# mippe_base.net
KiCad netlist of a schematic drawn in EAGLE
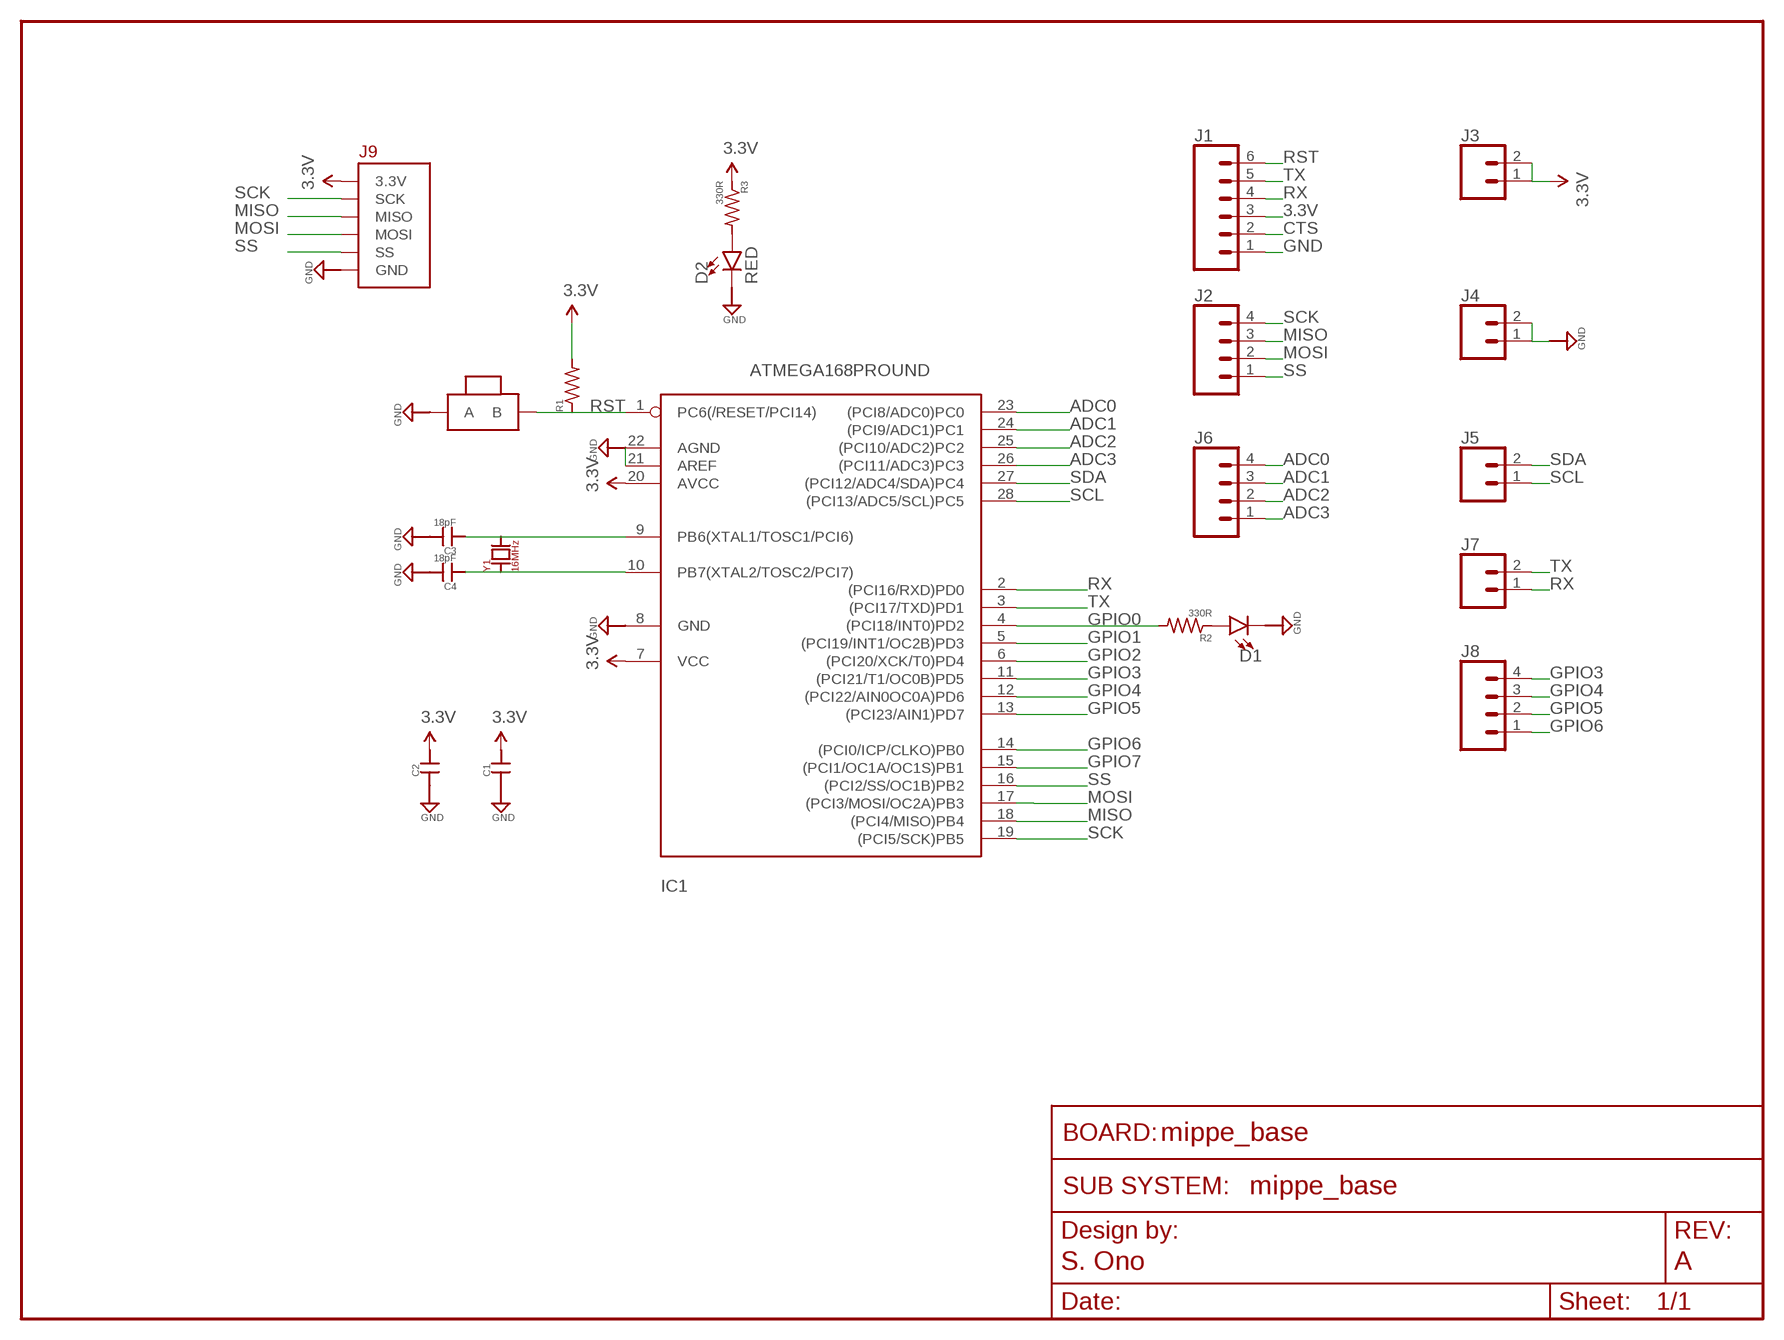
[diagram p0: schematic, sheet 1]

(export (version "E")
  (design (tool "Eeschema 10.0.6"))
  (components
    (comp (ref "C1")
      (value "CAP0603-CAP")
      (footprint "eagle-import:0603-CAP")
      (libsource (lib "eagle-import") (part "CAP0603-CAP"))
    )
    (comp (ref "C2")
      (value "CAP0603-CAP")
      (footprint "eagle-import:0603-CAP")
      (libsource (lib "eagle-import") (part "CAP0603-CAP"))
    )
    (comp (ref "C3")
      (value "18pF")
      (footprint "eagle-import:0603-CAP")
      (libsource (lib "eagle-import") (part "CAP0603-CAP"))
    )
    (comp (ref "C4")
      (value "18pF")
      (footprint "eagle-import:0603-CAP")
      (libsource (lib "eagle-import") (part "CAP0603-CAP"))
    )
    (comp (ref "D1")
      (value "LED0603")
      (footprint "eagle-import:LED-0603")
      (libsource (lib "eagle-import") (part "LED0603"))
    )
    (comp (ref "D2")
      (value "RED")
      (footprint "eagle-import:LED-0603")
      (libsource (lib "eagle-import") (part "LED0603"))
    )
    (comp (ref "IC1")
      (value "ATMEGA168PROUND")
      (footprint "eagle-import:DIL28-3-ROUND")
      (libsource (lib "eagle-import") (part "ATMEGA168PROUND"))
    )
    (comp (ref "J1")
      (value "CONN_06NO_SILK_FEMALE_PTH")
      (footprint "eagle-import:1X06_NO_SILK")
      (libsource (lib "eagle-import") (part "CONN_06NO_SILK_FEMALE_PTH"))
    )
    (comp (ref "J2")
      (value "CONN_041X04_NO_SILK")
      (footprint "eagle-import:1X04_NO_SILK")
      (libsource (lib "eagle-import") (part "CONN_041X04_NO_SILK"))
    )
    (comp (ref "J3")
      (value "CONN_021X02_NO_SILK")
      (footprint "eagle-import:1X02_NO_SILK")
      (libsource (lib "eagle-import") (part "CONN_021X02_NO_SILK"))
    )
    (comp (ref "J4")
      (value "CONN_021X02_NO_SILK")
      (footprint "eagle-import:1X02_NO_SILK")
      (libsource (lib "eagle-import") (part "CONN_021X02_NO_SILK"))
    )
    (comp (ref "J5")
      (value "CONN_021X02_NO_SILK")
      (footprint "eagle-import:1X02_NO_SILK")
      (libsource (lib "eagle-import") (part "CONN_021X02_NO_SILK"))
    )
    (comp (ref "J6")
      (value "CONN_041X04_NO_SILK")
      (footprint "eagle-import:1X04_NO_SILK")
      (libsource (lib "eagle-import") (part "CONN_041X04_NO_SILK"))
    )
    (comp (ref "J7")
      (value "CONN_021X02_NO_SILK")
      (footprint "eagle-import:1X02_NO_SILK")
      (libsource (lib "eagle-import") (part "CONN_021X02_NO_SILK"))
    )
    (comp (ref "J8")
      (value "CONN_041X04_NO_SILK")
      (footprint "eagle-import:1X04_NO_SILK")
      (libsource (lib "eagle-import") (part "CONN_041X04_NO_SILK"))
    )
    (comp (ref "J9")
      (value "BURNIN")
      (footprint "eagle-import:BURNIN")
      (libsource (lib "eagle-import") (part "BURNIN"))
    )
    (comp (ref "R1")
      (value "R-US_R0603")
      (footprint "eagle-import:R0603")
      (fields (field (name "MANUFACTURER") "Rohm Semiconductor"))
      (libsource (lib "eagle-import") (part "R-US_R0603"))
    )
    (comp (ref "R2")
      (value "330R")
      (footprint "eagle-import:R0603")
      (fields (field (name "MANUFACTURER") "Rohm Semiconductor"))
      (libsource (lib "eagle-import") (part "R-US_R0603"))
    )
    (comp (ref "R3")
      (value "330R")
      (footprint "eagle-import:R0603")
      (fields (field (name "MANUFACTURER") "Rohm Semiconductor"))
      (libsource (lib "eagle-import") (part "R-US_R0603"))
    )
    (comp (ref "SW1")
      (value "BTN-PTS810")
      (footprint "eagle-import:BTN_PTS810")
      (libsource (lib "eagle-import") (part "BTN-PTS810"))
    )
    (comp (ref "Y1")
      (value "16MHz")
      (footprint "eagle-import:HC-49")
      (libsource (lib "eagle-import") (part "CRYSTAL"))
    )
  )
  (nets
    (net (code "1") (name "/ADC0") (class "Default")
      (node (ref "IC1") (pin "23") (pinfunction "(PCI8/ADC0)PC0_23") (pintype "bidirectional"))
      (node (ref "J6") (pin "4") (pinfunction "4_4") (pintype "passive"))
    )
    (net (code "2") (name "/ADC1") (class "Default")
      (node (ref "IC1") (pin "24") (pinfunction "(PCI9/ADC1)PC1_24") (pintype "bidirectional"))
      (node (ref "J6") (pin "3") (pinfunction "3_3") (pintype "passive"))
    )
    (net (code "3") (name "/ADC2") (class "Default")
      (node (ref "IC1") (pin "25") (pinfunction "(PCI10/ADC2)PC2_25") (pintype "bidirectional"))
      (node (ref "J6") (pin "2") (pinfunction "2_2") (pintype "passive"))
    )
    (net (code "4") (name "/ADC3") (class "Default")
      (node (ref "IC1") (pin "26") (pinfunction "(PCI11/ADC3)PC3_26") (pintype "bidirectional"))
      (node (ref "J6") (pin "1") (pinfunction "1_1") (pintype "passive"))
    )
    (net (code "5") (name "/CTS") (class "Default")
      (node (ref "J1") (pin "2") (pinfunction "2_2") (pintype "passive"))
    )
    (net (code "6") (name "/GPIO0") (class "Default")
      (node (ref "IC1") (pin "4") (pinfunction "(PCI18/INT0)PD2_4") (pintype "bidirectional"))
      (node (ref "R2") (pin "2") (pinfunction "2_2") (pintype "passive"))
    )
    (net (code "7") (name "/GPIO1") (class "Default")
      (node (ref "IC1") (pin "5") (pinfunction "(PCI19/INT1/OC2B)PD3_5") (pintype "bidirectional"))
    )
    (net (code "8") (name "/GPIO2") (class "Default")
      (node (ref "IC1") (pin "6") (pinfunction "(PCI20/XCK/T0)PD4_6") (pintype "bidirectional"))
    )
    (net (code "9") (name "/GPIO3") (class "Default")
      (node (ref "IC1") (pin "11") (pinfunction "(PCI21/T1/OC0B)PD5_11") (pintype "bidirectional"))
      (node (ref "J8") (pin "4") (pinfunction "4_4") (pintype "passive"))
    )
    (net (code "10") (name "/GPIO4") (class "Default")
      (node (ref "IC1") (pin "12") (pinfunction "(PCI22/AIN0OC0A)PD6_12") (pintype "bidirectional"))
      (node (ref "J8") (pin "3") (pinfunction "3_3") (pintype "passive"))
    )
    (net (code "11") (name "/GPIO5") (class "Default")
      (node (ref "IC1") (pin "13") (pinfunction "(PCI23/AIN1)PD7_13") (pintype "bidirectional"))
      (node (ref "J8") (pin "2") (pinfunction "2_2") (pintype "passive"))
    )
    (net (code "12") (name "/GPIO6") (class "Default")
      (node (ref "IC1") (pin "14") (pinfunction "(PCI0/ICP/CLKO)PB0_14") (pintype "bidirectional"))
      (node (ref "J8") (pin "1") (pinfunction "1_1") (pintype "passive"))
    )
    (net (code "13") (name "/GPIO7") (class "Default")
      (node (ref "IC1") (pin "15") (pinfunction "(PCI1/OC1A/OC1S)PB1_15") (pintype "bidirectional"))
    )
    (net (code "14") (name "/MISO") (class "Default")
      (node (ref "IC1") (pin "18") (pinfunction "(PCI4/MISO)PB4_18") (pintype "bidirectional"))
      (node (ref "J2") (pin "3") (pinfunction "3_3") (pintype "passive"))
      (node (ref "J9") (pin "MISO") (pinfunction "MISO_MISO") (pintype "bidirectional"))
    )
    (net (code "15") (name "/MOSI") (class "Default")
      (node (ref "IC1") (pin "17") (pinfunction "(PCI3/MOSI/OC2A)PB3_17") (pintype "bidirectional"))
      (node (ref "J2") (pin "2") (pinfunction "2_2") (pintype "passive"))
      (node (ref "J9") (pin "MOSI") (pinfunction "MOSI_MOSI") (pintype "bidirectional"))
    )
    (net (code "16") (name "/RST") (class "Default")
      (node (ref "IC1") (pin "1") (pinfunction "PC6(/RESET/PCI14)_1") (pintype "bidirectional"))
      (node (ref "J1") (pin "6") (pinfunction "6_6") (pintype "passive"))
      (node (ref "R1") (pin "1") (pinfunction "1_1") (pintype "passive"))
      (node (ref "SW1") (pin "3") (pinfunction "B_3") (pintype "bidirectional"))
      (node (ref "SW1") (pin "4") (pinfunction "B_4") (pintype "bidirectional"))
    )
    (net (code "17") (name "/RX") (class "Default")
      (node (ref "IC1") (pin "2") (pinfunction "(PCI16/RXD)PD0_2") (pintype "bidirectional"))
      (node (ref "J1") (pin "4") (pinfunction "4_4") (pintype "passive"))
      (node (ref "J7") (pin "1") (pinfunction "1_1") (pintype "passive"))
    )
    (net (code "18") (name "/SCK") (class "Default")
      (node (ref "IC1") (pin "19") (pinfunction "(PCI5/SCK)PB5_19") (pintype "bidirectional"))
      (node (ref "J2") (pin "4") (pinfunction "4_4") (pintype "passive"))
      (node (ref "J9") (pin "SCK") (pinfunction "SCK_SCK") (pintype "bidirectional"))
    )
    (net (code "19") (name "/SCL") (class "Default")
      (node (ref "IC1") (pin "28") (pinfunction "(PCI13/ADC5/SCL)PC5_28") (pintype "bidirectional"))
      (node (ref "J5") (pin "1") (pinfunction "1_1") (pintype "passive"))
    )
    (net (code "20") (name "/SDA") (class "Default")
      (node (ref "IC1") (pin "27") (pinfunction "(PCI12/ADC4/SDA)PC4_27") (pintype "bidirectional"))
      (node (ref "J5") (pin "2") (pinfunction "2_2") (pintype "passive"))
    )
    (net (code "21") (name "/SS") (class "Default")
      (node (ref "IC1") (pin "16") (pinfunction "(PCI2/SS/OC1B)PB2_16") (pintype "bidirectional"))
      (node (ref "J2") (pin "1") (pinfunction "1_1") (pintype "passive"))
      (node (ref "J9") (pin "SS") (pinfunction "SS_SS") (pintype "bidirectional"))
    )
    (net (code "22") (name "/TX") (class "Default")
      (node (ref "IC1") (pin "3") (pinfunction "(PCI17/TXD)PD1_3") (pintype "bidirectional"))
      (node (ref "J1") (pin "5") (pinfunction "5_5") (pintype "passive"))
      (node (ref "J7") (pin "2") (pinfunction "2_2") (pintype "passive"))
    )
    (net (code "23") (name "3.3V") (class "Default")
      (node (ref "C1") (pin "2") (pinfunction "2_2") (pintype "passive"))
      (node (ref "C2") (pin "2") (pinfunction "2_2") (pintype "passive"))
      (node (ref "IC1") (pin "20") (pinfunction "AVCC_20") (pintype "bidirectional"))
      (node (ref "IC1") (pin "7") (pinfunction "VCC_7") (pintype "bidirectional"))
      (node (ref "J1") (pin "3") (pinfunction "3_3") (pintype "passive"))
      (node (ref "J3") (pin "1") (pinfunction "1_1") (pintype "passive"))
      (node (ref "J3") (pin "2") (pinfunction "2_2") (pintype "passive"))
      (node (ref "J9") (pin "3.3V") (pinfunction "3.3V_3.3V") (pintype "power_in"))
      (node (ref "R1") (pin "2") (pinfunction "2_2") (pintype "passive"))
      (node (ref "R3") (pin "1") (pinfunction "1_1") (pintype "passive"))
    )
    (net (code "24") (name "GND") (class "Default")
      (node (ref "C1") (pin "1") (pinfunction "1_1") (pintype "passive"))
      (node (ref "C2") (pin "1") (pinfunction "1_1") (pintype "passive"))
      (node (ref "C3") (pin "2") (pinfunction "2_2") (pintype "passive"))
      (node (ref "C4") (pin "2") (pinfunction "2_2") (pintype "passive"))
      (node (ref "D1") (pin "C") (pinfunction "C_C") (pintype "passive"))
      (node (ref "D2") (pin "C") (pinfunction "C_C") (pintype "passive"))
      (node (ref "IC1") (pin "21") (pinfunction "AREF_21") (pintype "bidirectional"))
      (node (ref "IC1") (pin "22") (pinfunction "AGND_22") (pintype "bidirectional"))
      (node (ref "IC1") (pin "8") (pinfunction "GND_8") (pintype "bidirectional"))
      (node (ref "J1") (pin "1") (pinfunction "1_1") (pintype "passive"))
      (node (ref "J4") (pin "1") (pinfunction "1_1") (pintype "passive"))
      (node (ref "J4") (pin "2") (pinfunction "2_2") (pintype "passive"))
      (node (ref "J9") (pin "GND") (pinfunction "GND_GND") (pintype "power_in"))
      (node (ref "SW1") (pin "1") (pinfunction "A_1") (pintype "bidirectional"))
      (node (ref "SW1") (pin "2") (pinfunction "A_2") (pintype "bidirectional"))
    )
    (net (code "25") (name "Net-(D1-PadA)") (class "Default")
      (node (ref "D1") (pin "A") (pinfunction "A_A") (pintype "passive"))
      (node (ref "R2") (pin "1") (pinfunction "1_1") (pintype "passive"))
    )
    (net (code "26") (name "Net-(D2-PadA)") (class "Default")
      (node (ref "D2") (pin "A") (pinfunction "A_A") (pintype "passive"))
      (node (ref "R3") (pin "2") (pinfunction "2_2") (pintype "passive"))
    )
    (net (code "27") (name "Net-(IC1-PB6(XTAL1{slash}TOSC1{slash}PCI6))") (class "Default")
      (node (ref "C3") (pin "1") (pinfunction "1_1") (pintype "passive"))
      (node (ref "IC1") (pin "9") (pinfunction "PB6(XTAL1/TOSC1/PCI6)_9") (pintype "bidirectional"))
      (node (ref "Y1") (pin "B") (pinfunction "B_B") (pintype "passive"))
    )
    (net (code "28") (name "Net-(IC1-PB7(XTAL2{slash}TOSC2{slash}PCI7))") (class "Default")
      (node (ref "C4") (pin "1") (pinfunction "1_1") (pintype "passive"))
      (node (ref "IC1") (pin "10") (pinfunction "PB7(XTAL2/TOSC2/PCI7)_10") (pintype "bidirectional"))
      (node (ref "Y1") (pin "A") (pinfunction "A_A") (pintype "passive"))
    )
  )
)
